# POWER_SUPPLY.net
KiCad netlist of a schematic drawn in Altium Designer
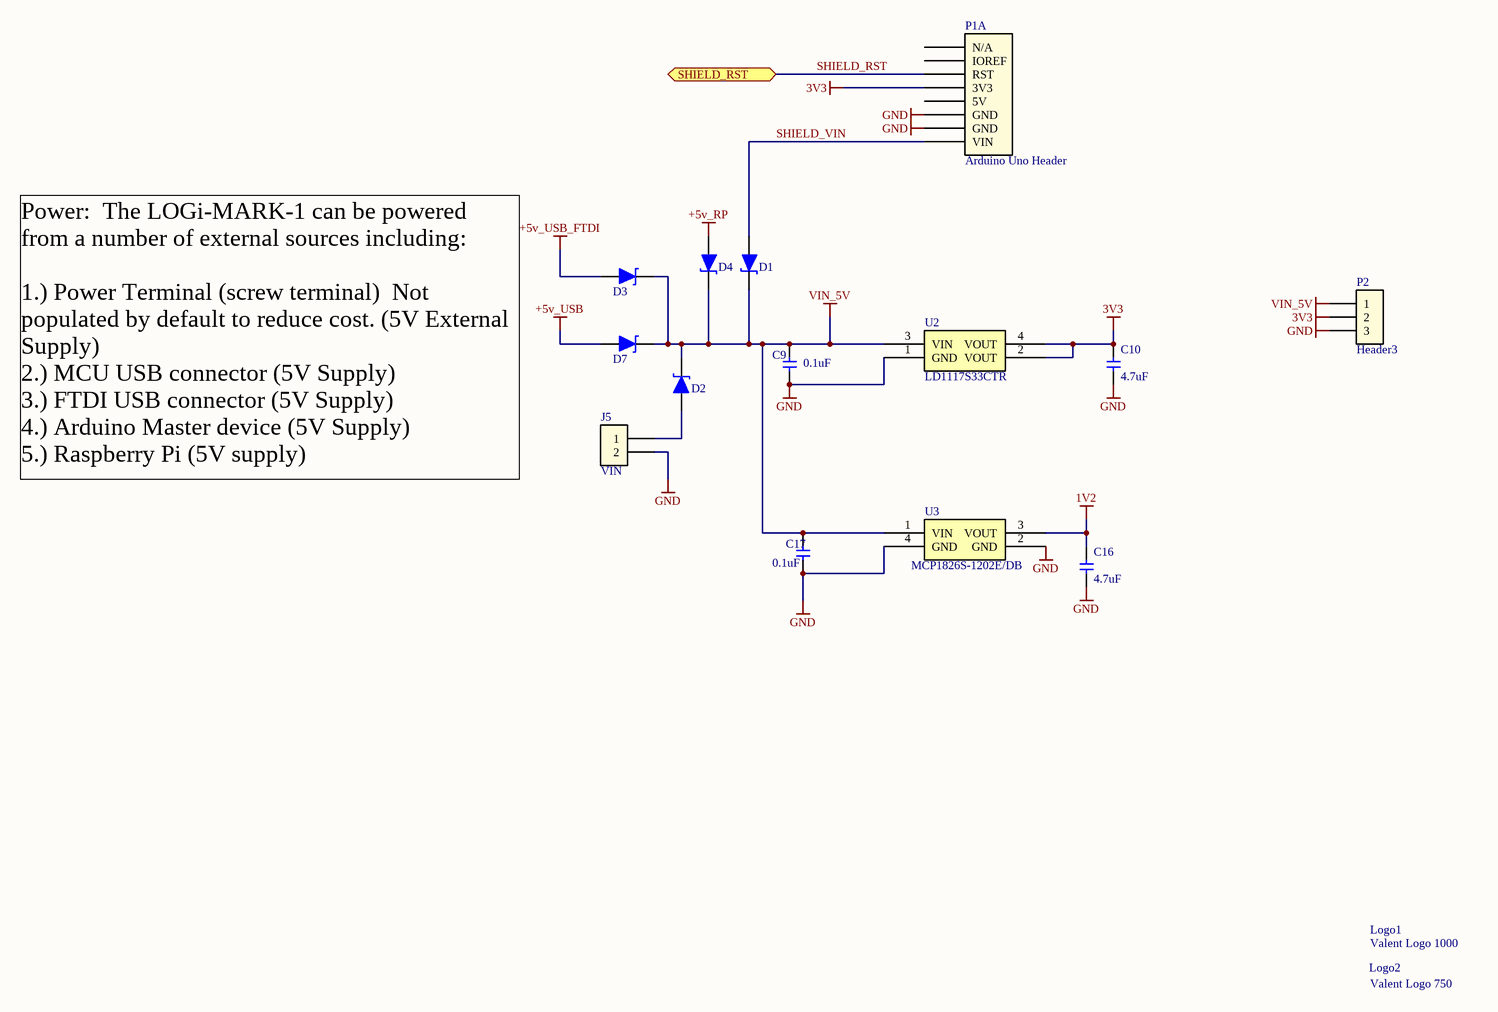
[diagram p0: POWER_SUPPLY.SchDoc]

(export (version "E")
  (design (tool "Eeschema 10.0.6"))
  (components
    (comp (ref "C9")
      (value "0.1uF")
      (footprint "C0603")
      (description "CAP CER .1UF 50V 10% X7R 0603")
      (fields
        (field (name "MANUFACTURER") "Murata Electronics North America")
        (field (name "MANUFACTURER PART NUMBER") "GRM188R71H104KA93D")
      )
      (libsource (lib "Capacitors") (part "GRM188R71H104KA93D"))
    )
    (comp (ref "C10")
      (value "4.7uF")
      (footprint "C0603")
      (description "CAP CER 4.7UF 6.3V X5R 0603")
      (fields
        (field (name "MANUFACTURER") "Murata Electronics North America")
        (field (name "MANUFACTURER PART NUMBER") "GRM188R60J475KE19D")
      )
      (libsource (lib "eCapacitors") (part "GRM188R60J475KE19D"))
    )
    (comp (ref "C16")
      (value "4.7uF")
      (footprint "C0603")
      (description "CAP CER 4.7UF 6.3V X5R 0603")
      (fields
        (field (name "MANUFACTURER") "Murata Electronics North America")
        (field (name "MANUFACTURER PART NUMBER") "GRM188R60J475KE19D")
      )
      (libsource (lib "eCapacitors") (part "GRM188R60J475KE19D"))
    )
    (comp (ref "C17")
      (value "0.1uF")
      (footprint "C0603")
      (description "CAP CER .1UF 50V 10% X7R 0603")
      (fields
        (field (name "MANUFACTURER") "Murata Electronics North America")
        (field (name "MANUFACTURER PART NUMBER") "GRM188R71H104KA93D")
      )
      (libsource (lib "Capacitors") (part "GRM188R71H104KA93D"))
    )
    (comp (ref "D1")
      (value "RB161M-20TR")
      (footprint "SOD-123")
      (description "DIODE SCHOTTKY 25V 1A SOD123")
      (fields
        (field (name "MANUFACTURER") "Diodes Inc")
        (field (name "MANUFACTURER PART NUMBER") "Rohm Semiconductor")
        (field (name "SOURCE") "Digikey")
      )
      (libsource (lib "eDiode") (part "RB161M-20TR"))
    )
    (comp (ref "D2")
      (value "RB161M-20TR")
      (footprint "SOD-123")
      (description "DIODE SCHOTTKY 25V 1A SOD123")
      (fields
        (field (name "MANUFACTURER") "Diodes Inc")
        (field (name "MANUFACTURER PART NUMBER") "Rohm Semiconductor")
        (field (name "SOURCE") "Digikey")
      )
      (libsource (lib "eDiode") (part "RB161M-20TR"))
    )
    (comp (ref "D3")
      (value "RB161M-20TR")
      (footprint "SOD-123")
      (description "DIODE SCHOTTKY 25V 1A SOD123")
      (fields
        (field (name "MANUFACTURER") "Diodes Inc")
        (field (name "MANUFACTURER PART NUMBER") "Rohm Semiconductor")
        (field (name "SOURCE") "Digikey")
      )
      (libsource (lib "eDiode") (part "RB161M-20TR"))
    )
    (comp (ref "D4")
      (value "RB161M-20TR")
      (footprint "ediode:SOD-123")
      (description "DIODE SCHOTTKY 25V 1A SOD123")
      (fields
        (field (name "MANUFACTURER") "Diodes Inc")
        (field (name "MANUFACTURER PART NUMBER") "Rohm Semiconductor")
        (field (name "SOURCE") "Digikey")
      )
      (libsource (lib "eDiode") (part "RB161M-20TR"))
    )
    (comp (ref "D7")
      (value "RB161M-20TR")
      (footprint "SOD-123")
      (description "DIODE SCHOTTKY 25V 1A SOD123")
      (fields
        (field (name "MANUFACTURER") "Diodes Inc")
        (field (name "MANUFACTURER PART NUMBER") "Rohm Semiconductor")
        (field (name "SOURCE") "Digikey")
      )
      (libsource (lib "eDiode") (part "RB161M-20TR"))
    )
    (comp (ref "J5")
      (value "VIN")
      (footprint "HEADER_2_40_100 THRU SIP")
      (description "Header 2 pin")
      (libsource (lib "mConnector") (part "Header2"))
    )
    (comp (ref "Logo1")
      (value "Valent Logo 1000")
      (footprint "ValentFX_1000")
      (libsource (lib "mLogos") (part "Valent Logo 1000"))
    )
    (comp (ref "Logo2")
      (value "Valent Logo 750")
      (footprint "ValentFX_750")
      (libsource (lib "mLogos") (part "Valent Logo 750"))
    )
    (comp (ref "P1")
      (value "Arduino Uno Header")
      (footprint "Arduino Shield - smaller Thru")
      (description "Arduino Duem Header")
      (libsource (lib "eConnector") (part "Arduino Shield"))
    )
    (comp (ref "P2")
      (value "Header3")
      (footprint "HEADER_3_40_100 THRU SIP")
      (description "Header  pin")
      (libsource (lib "mConnector") (part "Header3"))
    )
    (comp (ref "U2")
      (value "LD1117S33CTR")
      (footprint "SOT223")
      (description "IC REG LDO 3.3V 950MA SOT-223")
      (fields (field (name "MANUFACTURER") "STMicroelectronics"))
      (libsource (lib "eIC") (part "LD1117S33CTR"))
    )
    (comp (ref "U3")
      (value "MCP1826S-1202E/DB")
      (footprint "SOT223")
      (description "IC LDO REG 1A 1.2V SOT223-3")
      (fields (field (name "MANUFACTURER") "Microchip Technology"))
      (libsource (lib "eIC") (part "MCP1826S-1202E/DB"))
    )
  )
  (nets
    (net (code "1") (name "+5v_RP") (class "Default")
      (node (ref "D4") (pin "2") (pinfunction "A_2") (pintype "passive"))
    )
    (net (code "2") (name "+5v_USB") (class "Default")
      (node (ref "D7") (pin "2") (pinfunction "A_2") (pintype "passive"))
    )
    (net (code "3") (name "+5v_USB_FTDI") (class "Default")
      (node (ref "D3") (pin "2") (pinfunction "A_2") (pintype "passive"))
    )
    (net (code "4") (name "/SHIELD_RST") (class "Default")
      (node (ref "P1") (pin "A1") (pinfunction "RST_A1") (pintype "passive"))
    )
    (net (code "5") (name "/SHIELD_VIN") (class "Default")
      (node (ref "D1") (pin "2") (pinfunction "A_2") (pintype "passive"))
      (node (ref "P1") (pin "A6") (pinfunction "VIN_A6") (pintype "passive"))
    )
    (net (code "6") (name "1V2") (class "Default")
      (node (ref "C16") (pin "2") (pinfunction "2_2") (pintype "passive"))
      (node (ref "U3") (pin "3") (pinfunction "VOUT_3") (pintype "passive"))
    )
    (net (code "7") (name "3V3") (class "Default")
      (node (ref "C10") (pin "2") (pinfunction "2_2") (pintype "passive"))
      (node (ref "P1") (pin "A2") (pinfunction "3V3_A2") (pintype "passive"))
      (node (ref "P2") (pin "2") (pinfunction "2_2") (pintype "passive"))
      (node (ref "U2") (pin "2") (pinfunction "VOUT_2") (pintype "passive"))
      (node (ref "U2") (pin "4") (pinfunction "VOUT_4") (pintype "passive"))
    )
    (net (code "8") (name "GND") (class "Default")
      (node (ref "C10") (pin "1") (pinfunction "1_1") (pintype "passive"))
      (node (ref "C16") (pin "1") (pinfunction "1_1") (pintype "passive"))
      (node (ref "C17") (pin "1") (pinfunction "1_1") (pintype "passive"))
      (node (ref "C9") (pin "1") (pinfunction "1_1") (pintype "passive"))
      (node (ref "J5") (pin "2") (pinfunction "2_2") (pintype "passive"))
      (node (ref "P1") (pin "A4") (pinfunction "GND_A4") (pintype "passive"))
      (node (ref "P1") (pin "A5") (pinfunction "GND_A5") (pintype "passive"))
      (node (ref "P2") (pin "3") (pinfunction "3_3") (pintype "passive"))
      (node (ref "U2") (pin "1") (pinfunction "GND_1") (pintype "passive"))
      (node (ref "U3") (pin "2") (pinfunction "GND_2") (pintype "passive"))
      (node (ref "U3") (pin "4") (pinfunction "GND_4") (pintype "passive"))
    )
    (net (code "9") (name "Net-(D2-A)") (class "Default")
      (node (ref "D2") (pin "2") (pinfunction "A_2") (pintype "passive"))
      (node (ref "J5") (pin "1") (pinfunction "1_1") (pintype "passive"))
    )
    (net (code "10") (name "VIN_5V") (class "Default")
      (node (ref "C17") (pin "2") (pinfunction "2_2") (pintype "passive"))
      (node (ref "C9") (pin "2") (pinfunction "2_2") (pintype "passive"))
      (node (ref "D1") (pin "1") (pinfunction "C_1") (pintype "passive"))
      (node (ref "D2") (pin "1") (pinfunction "C_1") (pintype "passive"))
      (node (ref "D3") (pin "1") (pinfunction "C_1") (pintype "passive"))
      (node (ref "D4") (pin "1") (pinfunction "C_1") (pintype "passive"))
      (node (ref "D7") (pin "1") (pinfunction "C_1") (pintype "passive"))
      (node (ref "P2") (pin "1") (pinfunction "1_1") (pintype "passive"))
      (node (ref "U2") (pin "3") (pinfunction "VIN_3") (pintype "passive"))
      (node (ref "U3") (pin "1") (pinfunction "VIN_1") (pintype "passive"))
    )
    (net (code "11") (name "unconnected-(P1A-5V-PadA3)") (class "Default")
      (node (ref "P1") (pin "A3") (pinfunction "5V_A3") (pintype "passive"))
    )
    (net (code "12") (name "unconnected-(P1A-IOREF-PadA0)") (class "Default")
      (node (ref "P1") (pin "A0") (pinfunction "IOREF_A0") (pintype "passive"))
    )
    (net (code "13") (name "unconnected-(P1A-N{slash}A-PadA-1)") (class "Default")
      (node (ref "P1") (pin "A-1") (pinfunction "N/A_A-1") (pintype "passive"))
    )
  )
)
